# LEDs.net
KiCad netlist of a schematic drawn in Altium Designer
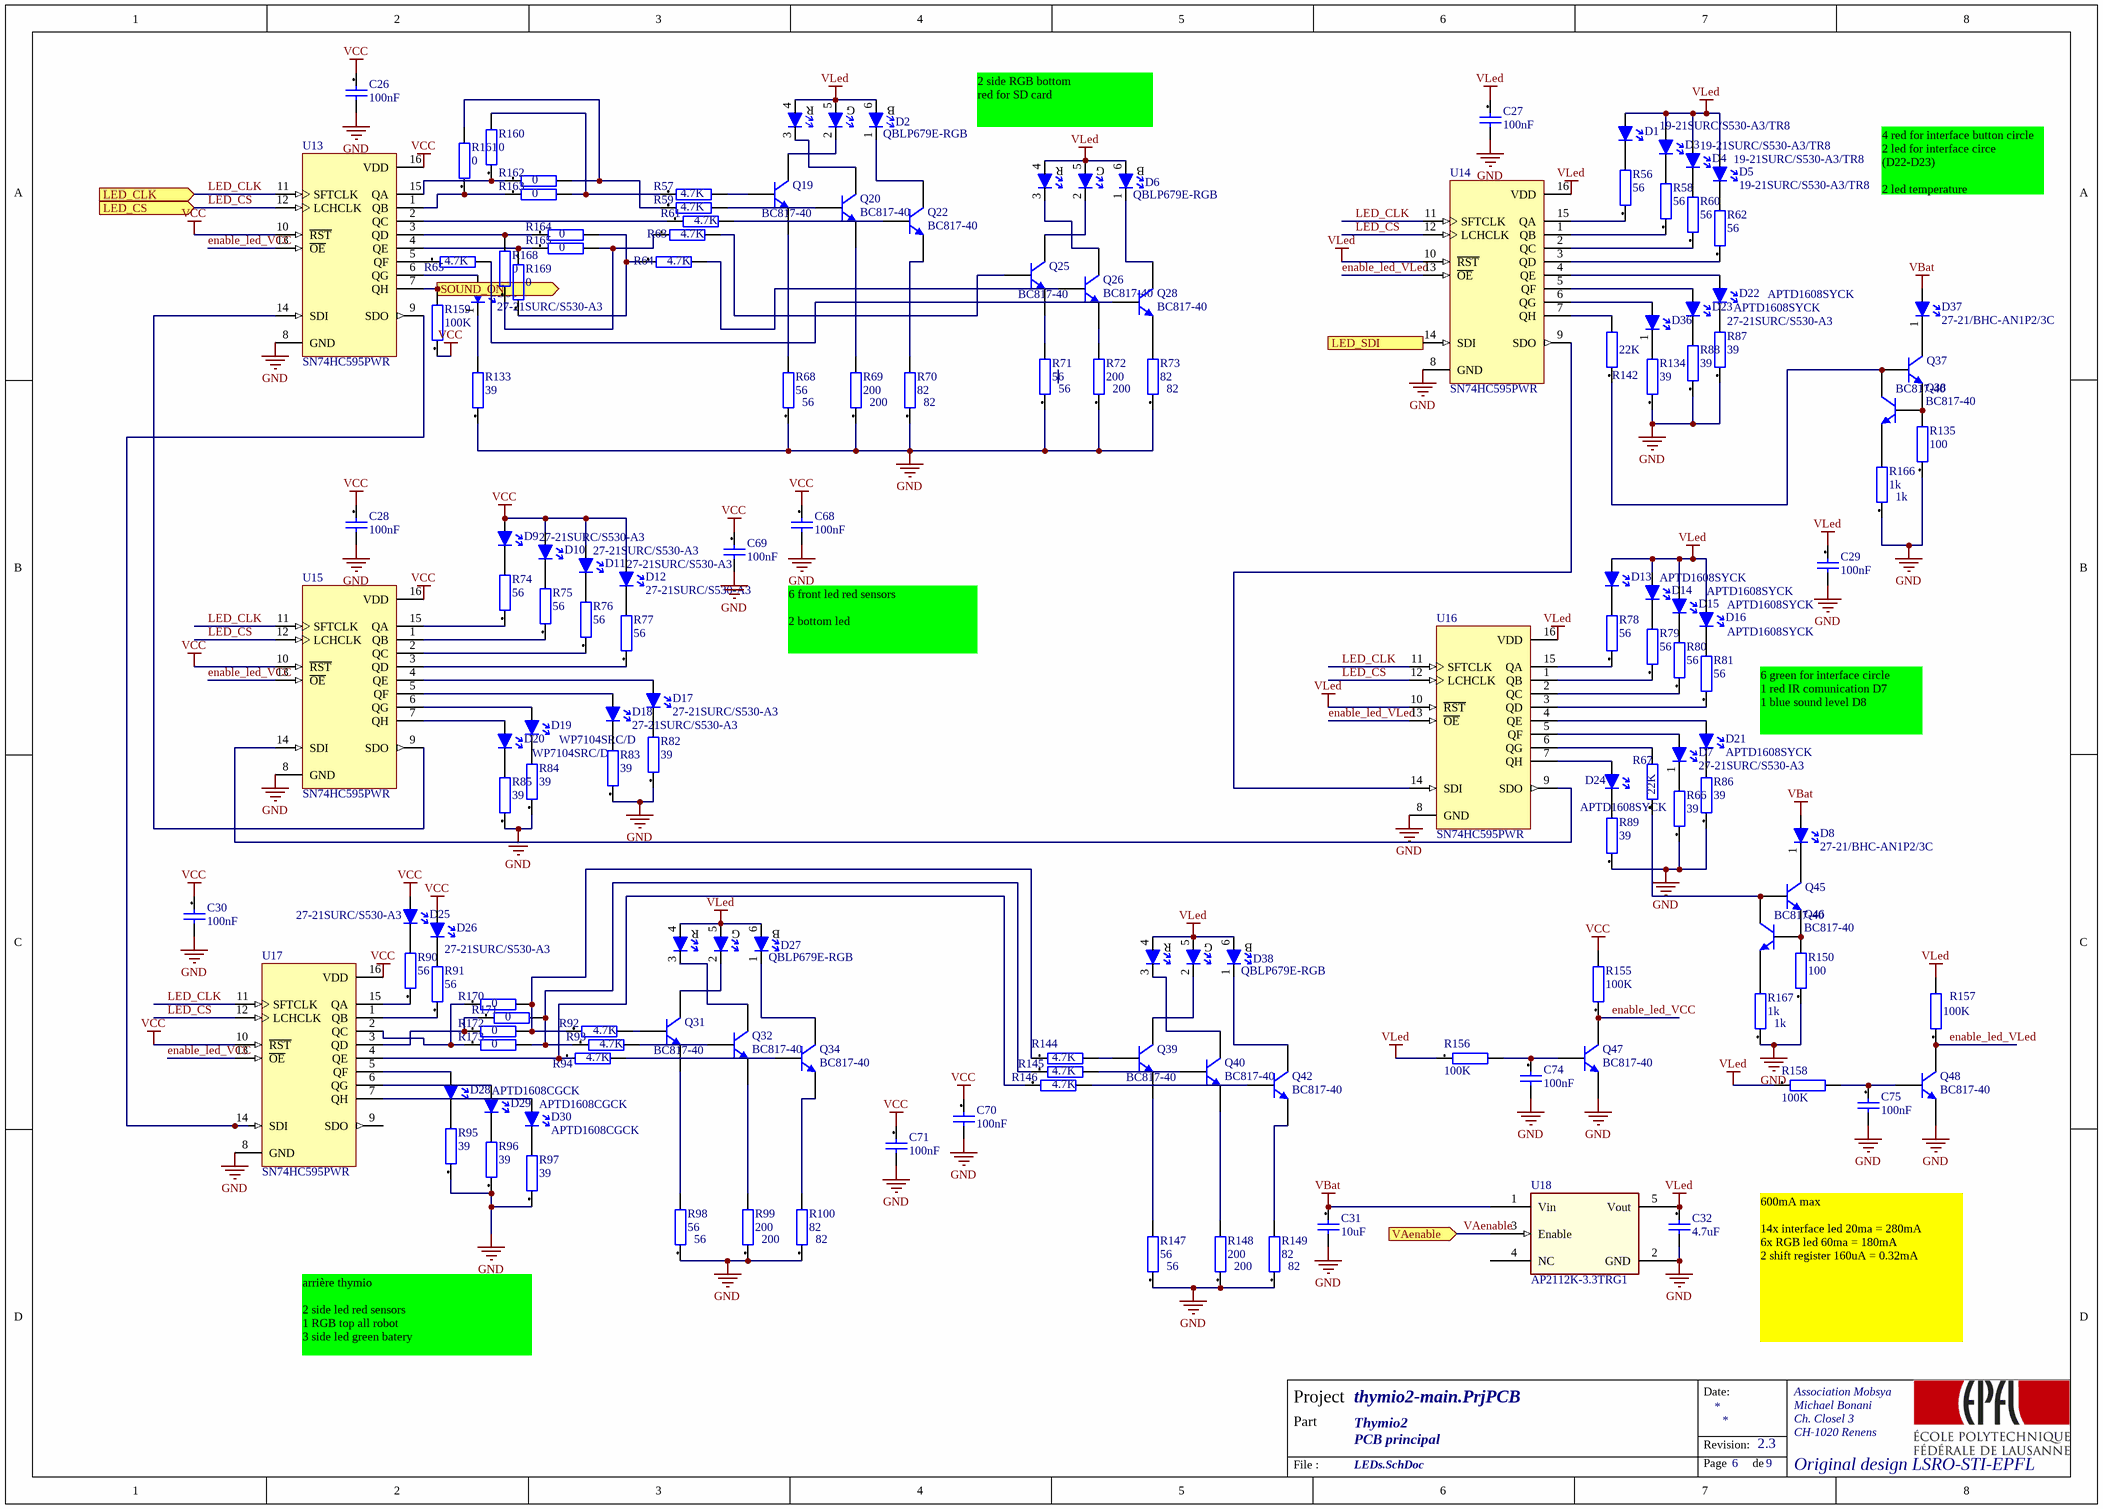
[diagram p0: LEDs.SchDoc]

(export (version "E")
  (design (tool "Eeschema 10.0.6"))
  (components
    (comp (ref "C26")
      (value "100nF")
      (footprint "CAPC1005X05N")
      (description "Capacitor")
      (fields (field (name "MANUFACTURER") "Kemet") (field (name "VOLTAGE") "50"))
      (libsource (lib "LSRO1Altium") (part "CAP-NP"))
    )
    (comp (ref "C27")
      (value "100nF")
      (footprint "CAPC1005X05N")
      (description "Capacitor")
      (fields (field (name "MANUFACTURER") "Kemet") (field (name "VOLTAGE") "50"))
      (libsource (lib "LSRO1Altium") (part "CAP-NP"))
    )
    (comp (ref "C28")
      (value "100nF")
      (footprint "CAPC1005X05N")
      (description "Capacitor")
      (fields (field (name "MANUFACTURER") "Kemet") (field (name "VOLTAGE") "50"))
      (libsource (lib "LSRO1Altium") (part "CAP-NP"))
    )
    (comp (ref "C29")
      (value "100nF")
      (footprint "CAPC1005X05N")
      (description "Capacitor")
      (fields (field (name "MANUFACTURER") "Kemet") (field (name "VOLTAGE") "50"))
      (libsource (lib "LSRO1Altium") (part "CAP-NP"))
    )
    (comp (ref "C30")
      (value "100nF")
      (footprint "CAPC1005X05N")
      (description "Capacitor")
      (fields (field (name "MANUFACTURER") "Kemet") (field (name "VOLTAGE") "50"))
      (libsource (lib "LSRO1Altium") (part "CAP-NP"))
    )
    (comp (ref "C31")
      (value "10uF")
      (footprint "CAPC1005X05N")
      (description "Capacitor")
      (fields (field (name "MANUFACTURER") "Kemet") (field (name "VOLTAGE") "6.3"))
      (libsource (lib "LSRO1Altium") (part "CAP-NP"))
    )
    (comp (ref "C32")
      (value "4.7uF")
      (footprint "CAPC1005X05N")
      (description "Capacitor")
      (fields (field (name "MANUFACTURER") "Kemet") (field (name "VOLTAGE") "6.3"))
      (libsource (lib "LSRO1Altium") (part "CAP-NP"))
    )
    (comp (ref "C68")
      (value "100nF")
      (footprint "CAPC1005X05N")
      (description "Capacitor")
      (fields (field (name "MANUFACTURER") "Kemet") (field (name "VOLTAGE") "50"))
      (libsource (lib "LSRO1Altium") (part "CAP-NP"))
    )
    (comp (ref "C69")
      (value "100nF")
      (footprint "CAPC1005X05N")
      (description "Capacitor")
      (fields (field (name "MANUFACTURER") "Kemet") (field (name "VOLTAGE") "50"))
      (libsource (lib "LSRO1Altium") (part "CAP-NP"))
    )
    (comp (ref "C70")
      (value "100nF")
      (footprint "CAPC1005X05N")
      (description "Capacitor")
      (fields (field (name "MANUFACTURER") "Kemet") (field (name "VOLTAGE") "50"))
      (libsource (lib "LSRO1Altium") (part "CAP-NP"))
    )
    (comp (ref "C71")
      (value "100nF")
      (footprint "CAPC1005X05N")
      (description "Capacitor")
      (fields (field (name "MANUFACTURER") "Kemet") (field (name "VOLTAGE") "50"))
      (libsource (lib "LSRO1Altium") (part "CAP-NP"))
    )
    (comp (ref "C74")
      (value "100nF")
      (footprint "CAPC1005X05N")
      (description "Capacitor")
      (fields (field (name "MANUFACTURER") "Kemet") (field (name "VOLTAGE") "50"))
      (libsource (lib "LSRO1Altium") (part "CAP-NP"))
    )
    (comp (ref "C75")
      (value "100nF")
      (footprint "CAPC1005X05N")
      (description "Capacitor")
      (fields (field (name "MANUFACTURER") "Kemet") (field (name "VOLTAGE") "50"))
      (libsource (lib "LSRO1Altium") (part "CAP-NP"))
    )
    (comp (ref "D1")
      (value "19-21SURC/S530-A3/TR8")
      (footprint "DIOC - DIOdeChip:DIOC1608X08N")
      (description "SMD Red 0603 2V@20ma 56 mcd")
      (fields (field (name "VERIFIEDCOMMENT") "ToDo"))
      (libsource (lib "LEDs") (part "LED"))
    )
    (comp (ref "D2")
      (value "QBLP679E-RGB")
      (footprint "thymio2-main:QBLP679E-RGB")
      (fields (field (name "VERIFIEDCOMMENT") "ToDo"))
      (libsource (lib "LEDs") (part "LED RGB SMD 2"))
    )
    (comp (ref "D3")
      (value "19-21SURC/S530-A3/TR8")
      (footprint "DIOC - DIOdeChip:DIOC1608X08N")
      (description "SMD Red 0603 2V@20ma 56 mcd")
      (fields (field (name "VERIFIEDCOMMENT") "ToDo"))
      (libsource (lib "LEDs") (part "LED"))
    )
    (comp (ref "D4")
      (value "19-21SURC/S530-A3/TR8")
      (footprint "DIOC - DIOdeChip:DIOC1608X08N")
      (description "SMD Red 0603 2V@20ma 56 mcd")
      (fields (field (name "VERIFIEDCOMMENT") "ToDo"))
      (libsource (lib "LEDs") (part "LED"))
    )
    (comp (ref "D5")
      (value "19-21SURC/S530-A3/TR8")
      (footprint "DIOC - DIOdeChip:DIOC1608X08N")
      (description "SMD Red 0603 2V@20ma 56 mcd")
      (fields (field (name "VERIFIEDCOMMENT") "ToDo"))
      (libsource (lib "LEDs") (part "LED"))
    )
    (comp (ref "D6")
      (value "QBLP679E-RGB")
      (footprint "thymio2-main:QBLP679E-RGB")
      (fields (field (name "VERIFIEDCOMMENT") "ToDo"))
      (libsource (lib "LEDs") (part "LED RGB SMD 2"))
    )
    (comp (ref "D7")
      (value "27-21SURC/S530-A3")
      (footprint "LEDs_Manufacturers:27-21 Everlight")
      (description "SMD Red led right angle mount 2V@20ma 57mcd")
      (fields (field (name "VERIFIEDCOMMENT") "ToDo"))
      (libsource (lib "") (part "LED_1"))
    )
    (comp (ref "D8")
      (value "27-21/BHC-AN1P2/3C")
      (footprint "LEDs_Manufacturers:27-21 Everlight Blue")
      (description "SMD Blue led right angle mount 3.3V@20ma 28mcd")
      (fields (field (name "VERIFIEDCOMMENT") "ToDo"))
      (libsource (lib "") (part "LED_1"))
    )
    (comp (ref "D9")
      (value "27-21SURC/S530-A3")
      (footprint "LEDs_Manufacturers:27-21 Everlight")
      (description "SMD Red led right angle mount 2V@20ma 57mcd")
      (fields (field (name "VERIFIEDCOMMENT") "ToDo"))
      (libsource (lib "LEDs") (part "LED"))
    )
    (comp (ref "D10")
      (value "27-21SURC/S530-A3")
      (footprint "LEDs_Manufacturers:27-21 Everlight")
      (description "SMD Red led right angle mount 2V@20ma 57mcd")
      (fields (field (name "VERIFIEDCOMMENT") "ToDo"))
      (libsource (lib "LEDs") (part "LED"))
    )
    (comp (ref "D11")
      (value "27-21SURC/S530-A3")
      (footprint "LEDs_Manufacturers:27-21 Everlight")
      (description "SMD Red led right angle mount 2V@20ma 57mcd")
      (fields (field (name "VERIFIEDCOMMENT") "ToDo"))
      (libsource (lib "LEDs") (part "LED"))
    )
    (comp (ref "D12")
      (value "27-21SURC/S530-A3")
      (footprint "LEDs_Manufacturers:27-21 Everlight")
      (description "SMD Red led right angle mount 2V@20ma 57mcd")
      (fields (field (name "VERIFIEDCOMMENT") "ToDo"))
      (libsource (lib "LEDs") (part "LED"))
    )
    (comp (ref "D13")
      (value "APTD1608SYCK")
      (footprint "DIOC - DIOdeChip:DIOC1608X08N")
      (description "LED standard - CMS Helios SMD Yellow 590nm 480mcd")
      (fields (field (name "VERIFIEDCOMMENT") "ToDo"))
      (libsource (lib "LEDs") (part "LED"))
    )
    (comp (ref "D14")
      (value "APTD1608SYCK")
      (footprint "DIOC - DIOdeChip:DIOC1608X08N")
      (description "LED standard - CMS Helios SMD Yellow 590nm 480mcd")
      (fields (field (name "VERIFIEDCOMMENT") "ToDo"))
      (libsource (lib "LEDs") (part "LED"))
    )
    (comp (ref "D15")
      (value "APTD1608SYCK")
      (footprint "DIOC - DIOdeChip:DIOC1608X08N")
      (description "LED standard - CMS Helios SMD Yellow 590nm 480mcd")
      (fields (field (name "VERIFIEDCOMMENT") "ToDo"))
      (libsource (lib "LEDs") (part "LED"))
    )
    (comp (ref "D16")
      (value "APTD1608SYCK")
      (footprint "DIOC - DIOdeChip:DIOC1608X08N")
      (description "LED standard - CMS Helios SMD Yellow 590nm 480mcd")
      (fields (field (name "VERIFIEDCOMMENT") "ToDo"))
      (libsource (lib "LEDs") (part "LED"))
    )
    (comp (ref "D17")
      (value "27-21SURC/S530-A3")
      (footprint "LEDs_Manufacturers:27-21 Everlight")
      (description "SMD Red led right angle mount 2V@20ma 57mcd")
      (fields (field (name "VERIFIEDCOMMENT") "ToDo"))
      (libsource (lib "LEDs") (part "LED"))
    )
    (comp (ref "D18")
      (value "27-21SURC/S530-A3")
      (footprint "LEDs_Manufacturers:27-21 Everlight")
      (description "SMD Red led right angle mount 2V@20ma 57mcd")
      (fields (field (name "VERIFIEDCOMMENT") "ToDo"))
      (libsource (lib "LEDs") (part "LED"))
    )
    (comp (ref "D19")
      (value "WP7104SRC/D")
      (footprint "LEDs_Manufacturers:Led_TH_3mm_20mm")
      (description "Red led 2V@20ma 57mcd")
      (fields (field (name "VERIFIEDCOMMENT") "ToDo"))
      (libsource (lib "LEDs") (part "LED"))
    )
    (comp (ref "D20")
      (value "WP7104SRC/D")
      (footprint "LEDs_Manufacturers:Led_TH_3mm_20mm")
      (description "Red led 2V@20ma 57mcd")
      (fields (field (name "VERIFIEDCOMMENT") "ToDo"))
      (libsource (lib "LEDs") (part "LED"))
    )
    (comp (ref "D21")
      (value "APTD1608SYCK")
      (footprint "DIOC - DIOdeChip:DIOC1608X08N")
      (description "LED standard - CMS Helios SMD Yellow 590nm 480mcd")
      (fields (field (name "VERIFIEDCOMMENT") "ToDo"))
      (libsource (lib "LEDs") (part "LED"))
    )
    (comp (ref "D22")
      (value "APTD1608SYCK")
      (footprint "DIOC - DIOdeChip:DIOC1608X08N")
      (description "LED standard - CMS Helios SMD Yellow 590nm 480mcd")
      (fields (field (name "VERIFIEDCOMMENT") "ToDo"))
      (libsource (lib "LEDs") (part "LED"))
    )
    (comp (ref "D23")
      (value "APTD1608SYCK")
      (footprint "DIOC - DIOdeChip:DIOC1608X08N")
      (description "LED standard - CMS Helios SMD Yellow 590nm 480mcd")
      (fields (field (name "VERIFIEDCOMMENT") "ToDo"))
      (libsource (lib "LEDs") (part "LED"))
    )
    (comp (ref "D24")
      (value "APTD1608SYCK")
      (footprint "DIOC - DIOdeChip:DIOC1608X08N")
      (description "LED standard - CMS Helios SMD Yellow 590nm 480mcd")
      (fields (field (name "VERIFIEDCOMMENT") "ToDo"))
      (libsource (lib "LEDs") (part "LED"))
    )
    (comp (ref "D25")
      (value "27-21SURC/S530-A3")
      (footprint "LEDs_Manufacturers:27-21 Everlight")
      (description "SMD Red led right angle mount 2V@20ma 57mcd")
      (fields (field (name "VERIFIEDCOMMENT") "ToDo"))
      (libsource (lib "LEDs") (part "LED"))
    )
    (comp (ref "D26")
      (value "27-21SURC/S530-A3")
      (footprint "LEDs_Manufacturers:27-21 Everlight")
      (description "SMD Red led right angle mount 2V@20ma 57mcd")
      (fields (field (name "VERIFIEDCOMMENT") "ToDo"))
      (libsource (lib "LEDs") (part "LED"))
    )
    (comp (ref "D27")
      (value "QBLP679E-RGB")
      (footprint "thymio2-main:QBLP679E-RGB")
      (fields (field (name "VERIFIEDCOMMENT") "ToDo"))
      (libsource (lib "LEDs") (part "LED RGB SMD 2"))
    )
    (comp (ref "D28")
      (value "APTD1608CGCK")
      (footprint "DIOC - DIOdeChip:DIOC1608X08N")
      (description "LED standard - CMS Helios SMD Green 570nm 230mcd")
      (fields (field (name "VERIFIEDCOMMENT") "ToDo"))
      (libsource (lib "LEDs") (part "LED"))
    )
    (comp (ref "D29")
      (value "APTD1608CGCK")
      (footprint "DIOC - DIOdeChip:DIOC1608X08N")
      (description "LED standard - CMS Helios SMD Green 570nm 230mcd")
      (fields (field (name "VERIFIEDCOMMENT") "ToDo"))
      (libsource (lib "LEDs") (part "LED"))
    )
    (comp (ref "D30")
      (value "APTD1608CGCK")
      (footprint "DIOC - DIOdeChip:DIOC1608X08N")
      (description "LED standard - CMS Helios SMD Green 570nm 230mcd")
      (fields (field (name "VERIFIEDCOMMENT") "ToDo"))
      (libsource (lib "LEDs") (part "LED"))
    )
    (comp (ref "D35")
      (value "27-21SURC/S530-A3")
      (footprint "LEDs_Manufacturers:27-21 Everlight")
      (description "SMD Red led right angle mount 2V@20ma 57mcd")
      (fields (field (name "VERIFIEDCOMMENT") "ToDo"))
      (libsource (lib "") (part "LED_1"))
    )
    (comp (ref "D36")
      (value "27-21SURC/S530-A3")
      (footprint "LEDs_Manufacturers:27-21 Everlight")
      (description "SMD Red led right angle mount 2V@20ma 57mcd")
      (fields (field (name "VERIFIEDCOMMENT") "ToDo"))
      (libsource (lib "") (part "LED_1"))
    )
    (comp (ref "D37")
      (value "27-21/BHC-AN1P2/3C")
      (footprint "LEDs_Manufacturers:27-21 Everlight Blue")
      (description "SMD Blue led right angle mount 3.3V@20ma 28mcd")
      (fields (field (name "VERIFIEDCOMMENT") "ToDo"))
      (libsource (lib "") (part "LED_1"))
    )
    (comp (ref "D38")
      (value "QBLP679E-RGB")
      (footprint "thymio2-main:QBLP679E-RGB")
      (fields (field (name "VERIFIEDCOMMENT") "ToDo"))
      (libsource (lib "LEDs") (part "LED RGB SMD 2"))
    )
    (comp (ref "Q19")
      (value "BC817-40")
      (footprint "SOT23_N")
      (description "NPN General-purpose Transistor")
      (fields (field (name "PUBLISHER") "Altium Limited"))
      (libsource (lib "Philips Discrete BJT - Low Power") (part "BC817-40"))
    )
    (comp (ref "Q20")
      (value "BC817-40")
      (footprint "SOT23_N")
      (description "NPN General-purpose Transistor")
      (fields (field (name "PUBLISHER") "Altium Limited"))
      (libsource (lib "Philips Discrete BJT - Low Power") (part "BC817-40"))
    )
    (comp (ref "Q22")
      (value "BC817-40")
      (footprint "SOT23_N")
      (description "NPN General-purpose Transistor")
      (fields (field (name "PUBLISHER") "Altium Limited"))
      (libsource (lib "Philips Discrete BJT - Low Power") (part "BC817-40"))
    )
    (comp (ref "Q25")
      (value "BC817-40")
      (footprint "SOT23_N")
      (description "NPN General-purpose Transistor")
      (fields (field (name "PUBLISHER") "Altium Limited"))
      (libsource (lib "Philips Discrete BJT - Low Power") (part "BC817-40"))
    )
    (comp (ref "Q26")
      (value "BC817-40")
      (footprint "SOT23_N")
      (description "NPN General-purpose Transistor")
      (fields (field (name "PUBLISHER") "Altium Limited"))
      (libsource (lib "Philips Discrete BJT - Low Power") (part "BC817-40"))
    )
    (comp (ref "Q28")
      (value "BC817-40")
      (footprint "SOT23_N")
      (description "NPN General-purpose Transistor")
      (fields (field (name "PUBLISHER") "Altium Limited"))
      (libsource (lib "Philips Discrete BJT - Low Power") (part "BC817-40"))
    )
    (comp (ref "Q31")
      (value "BC817-40")
      (footprint "SOT23_N")
      (description "NPN General-purpose Transistor")
      (fields (field (name "PUBLISHER") "Altium Limited"))
      (libsource (lib "Philips Discrete BJT - Low Power") (part "BC817-40"))
    )
    (comp (ref "Q32")
      (value "BC817-40")
      (footprint "SOT23_N")
      (description "NPN General-purpose Transistor")
      (fields (field (name "PUBLISHER") "Altium Limited"))
      (libsource (lib "Philips Discrete BJT - Low Power") (part "BC817-40"))
    )
    (comp (ref "Q34")
      (value "BC817-40")
      (footprint "SOT23_N")
      (description "NPN General-purpose Transistor")
      (fields (field (name "PUBLISHER") "Altium Limited"))
      (libsource (lib "Philips Discrete BJT - Low Power") (part "BC817-40"))
    )
    (comp (ref "Q37")
      (value "BC817-40")
      (footprint "SOT23_N")
      (description "NPN General-purpose Transistor")
      (fields (field (name "PUBLISHER") "Altium Limited"))
      (libsource (lib "Philips Discrete BJT - Low Power") (part "BC817-40"))
    )
    (comp (ref "Q38")
      (value "BC817-40")
      (footprint "SOT23_N")
      (description "NPN General-purpose Transistor")
      (fields (field (name "PUBLISHER") "Altium Limited"))
      (libsource (lib "Philips Discrete BJT - Low Power") (part "BC817-40"))
    )
    (comp (ref "Q39")
      (value "BC817-40")
      (footprint "SOT23_N")
      (description "NPN General-purpose Transistor")
      (fields (field (name "PUBLISHER") "Altium Limited"))
      (libsource (lib "Philips Discrete BJT - Low Power") (part "BC817-40"))
    )
    (comp (ref "Q40")
      (value "BC817-40")
      (footprint "SOT23_N")
      (description "NPN General-purpose Transistor")
      (fields (field (name "PUBLISHER") "Altium Limited"))
      (libsource (lib "Philips Discrete BJT - Low Power") (part "BC817-40"))
    )
    (comp (ref "Q42")
      (value "BC817-40")
      (footprint "SOT23_N")
      (description "NPN General-purpose Transistor")
      (fields (field (name "PUBLISHER") "Altium Limited"))
      (libsource (lib "Philips Discrete BJT - Low Power") (part "BC817-40"))
    )
    (comp (ref "Q45")
      (value "BC817-40")
      (footprint "SOT23_N")
      (description "NPN General-purpose Transistor")
      (fields (field (name "PUBLISHER") "Altium Limited"))
      (libsource (lib "Philips Discrete BJT - Low Power") (part "BC817-40"))
    )
    (comp (ref "Q46")
      (value "BC817-40")
      (footprint "SOT23_N")
      (description "NPN General-purpose Transistor")
      (fields (field (name "PUBLISHER") "Altium Limited"))
      (libsource (lib "Philips Discrete BJT - Low Power") (part "BC817-40"))
    )
    (comp (ref "Q47")
      (value "BC817-40")
      (footprint "SOT23_N")
      (description "NPN General-purpose Transistor")
      (fields (field (name "PUBLISHER") "Altium Limited"))
      (libsource (lib "Philips Discrete BJT - Low Power") (part "BC817-40"))
    )
    (comp (ref "Q48")
      (value "BC817-40")
      (footprint "SOT23_N")
      (description "NPN General-purpose Transistor")
      (fields (field (name "PUBLISHER") "Altium Limited"))
      (libsource (lib "Philips Discrete BJT - Low Power") (part "BC817-40"))
    )
    (comp (ref "R56")
      (value "56")
      (footprint "RESC1005X04N")
      (description "Resistor")
      (fields (field (name "TOLERANCE") "+/-1") (field (name "MANUFACTURER") "Vishay"))
      (libsource (lib "LSRO1Altium") (part "RES"))
    )
    (comp (ref "R57")
      (value "4.7K")
      (footprint "RESC1005X04N")
      (description "Resistor")
      (fields (field (name "TOLERANCE") "+/-1") (field (name "MANUFACTURER") "Vishay"))
      (libsource (lib "LSRO1Altium") (part "RES"))
    )
    (comp (ref "R58")
      (value "56")
      (footprint "RESC1005X04N")
      (description "Resistor")
      (fields (field (name "TOLERANCE") "+/-1") (field (name "MANUFACTURER") "Vishay"))
      (libsource (lib "LSRO1Altium") (part "RES"))
    )
    (comp (ref "R59")
      (value "4.7K")
      (footprint "RESC1005X04N")
      (description "Resistor")
      (fields (field (name "TOLERANCE") "+/-1") (field (name "MANUFACTURER") "Vishay"))
      (libsource (lib "LSRO1Altium") (part "RES"))
    )
    (comp (ref "R60")
      (value "56")
      (footprint "RESC1005X04N")
      (description "Resistor")
      (fields (field (name "TOLERANCE") "+/-1") (field (name "MANUFACTURER") "Vishay"))
      (libsource (lib "LSRO1Altium") (part "RES"))
    )
    (comp (ref "R61")
      (value "4.7K")
      (footprint "RESC1005X04N")
      (description "Resistor")
      (fields (field (name "TOLERANCE") "+/-1") (field (name "MANUFACTURER") "Vishay"))
      (libsource (lib "LSRO1Altium") (part "RES"))
    )
    (comp (ref "R62")
      (value "56")
      (footprint "RESC1005X04N")
      (description "Resistor")
      (fields (field (name "TOLERANCE") "+/-1") (field (name "MANUFACTURER") "Vishay"))
      (libsource (lib "LSRO1Altium") (part "RES"))
    )
    (comp (ref "R63")
      (value "4.7K")
      (footprint "RESC1005X04N")
      (description "Resistor")
      (fields (field (name "TOLERANCE") "+/-1") (field (name "MANUFACTURER") "Vishay"))
      (libsource (lib "LSRO1Altium") (part "RES"))
    )
    (comp (ref "R64")
      (value "4.7K")
      (footprint "RESC1005X04N")
      (description "Resistor")
      (fields (field (name "TOLERANCE") "+/-1") (field (name "MANUFACTURER") "Vishay"))
      (libsource (lib "LSRO1Altium") (part "RES"))
    )
    (comp (ref "R65")
      (value "4.7K")
      (footprint "RESC1005X04N")
      (description "Resistor")
      (fields (field (name "TOLERANCE") "+/-1") (field (name "MANUFACTURER") "Vishay"))
      (libsource (lib "LSRO1Altium") (part "RES"))
    )
    (comp (ref "R66")
      (value "39")
      (footprint "RESC1005X04N")
      (description "Resistor")
      (fields (field (name "TOLERANCE") "+/-1") (field (name "MANUFACTURER") "Vishay"))
      (libsource (lib "LSRO1Altium") (part "RES"))
    )
    (comp (ref "R67")
      (value "22K")
      (footprint "RESC1005X04N")
      (description "Resistor")
      (fields (field (name "TOLERANCE") "+/-1") (field (name "MANUFACTURER") "Vishay"))
      (libsource (lib "LSRO1Altium") (part "RES"))
    )
    (comp (ref "R68")
      (value "56")
      (footprint "RESC1005X04N")
      (fields (field (name "ALTIUM_VALUE") "56"))
      (libsource (lib "Passifs") (part "RES"))
    )
    (comp (ref "R69")
      (value "200")
      (footprint "RESC1005X04N")
      (fields (field (name "ALTIUM_VALUE") "200"))
      (libsource (lib "Passifs") (part "RES"))
    )
    (comp (ref "R70")
      (value "82")
      (footprint "RESC1005X04N")
      (fields (field (name "ALTIUM_VALUE") "82"))
      (libsource (lib "Passifs") (part "RES"))
    )
    (comp (ref "R71")
      (value "56")
      (footprint "RESC1005X04N")
      (fields (field (name "ALTIUM_VALUE") "56"))
      (libsource (lib "Passifs") (part "RES"))
    )
    (comp (ref "R72")
      (value "200")
      (footprint "RESC1005X04N")
      (fields (field (name "ALTIUM_VALUE") "200"))
      (libsource (lib "Passifs") (part "RES"))
    )
    (comp (ref "R73")
      (value "82")
      (footprint "RESC1005X04N")
      (fields (field (name "ALTIUM_VALUE") "82"))
      (libsource (lib "Passifs") (part "RES"))
    )
    (comp (ref "R74")
      (value "56")
      (footprint "RESC1005X04N")
      (description "Resistor")
      (fields (field (name "TOLERANCE") "+/-1") (field (name "MANUFACTURER") "Vishay"))
      (libsource (lib "LSRO1Altium") (part "RES"))
    )
    (comp (ref "R75")
      (value "56")
      (footprint "RESC1005X04N")
      (description "Resistor")
      (fields (field (name "TOLERANCE") "+/-1") (field (name "MANUFACTURER") "Vishay"))
      (libsource (lib "LSRO1Altium") (part "RES"))
    )
    (comp (ref "R76")
      (value "56")
      (footprint "RESC1005X04N")
      (description "Resistor")
      (fields (field (name "TOLERANCE") "+/-1") (field (name "MANUFACTURER") "Vishay"))
      (libsource (lib "LSRO1Altium") (part "RES"))
    )
    (comp (ref "R77")
      (value "56")
      (footprint "RESC1005X04N")
      (description "Resistor")
      (fields (field (name "TOLERANCE") "+/-1") (field (name "MANUFACTURER") "Vishay"))
      (libsource (lib "LSRO1Altium") (part "RES"))
    )
    (comp (ref "R78")
      (value "56")
      (footprint "RESC1005X04N")
      (description "Resistor")
      (fields (field (name "TOLERANCE") "+/-1") (field (name "MANUFACTURER") "Vishay"))
      (libsource (lib "LSRO1Altium") (part "RES"))
    )
    (comp (ref "R79")
      (value "56")
      (footprint "RESC1005X04N")
      (description "Resistor")
      (fields (field (name "TOLERANCE") "+/-1") (field (name "MANUFACTURER") "Vishay"))
      (libsource (lib "LSRO1Altium") (part "RES"))
    )
    (comp (ref "R80")
      (value "56")
      (footprint "RESC1005X04N")
      (description "Resistor")
      (fields (field (name "TOLERANCE") "+/-1") (field (name "MANUFACTURER") "Vishay"))
      (libsource (lib "LSRO1Altium") (part "RES"))
    )
    (comp (ref "R81")
      (value "56")
      (footprint "RESC1005X04N")
      (description "Resistor")
      (fields (field (name "TOLERANCE") "+/-1") (field (name "MANUFACTURER") "Vishay"))
      (libsource (lib "LSRO1Altium") (part "RES"))
    )
    (comp (ref "R82")
      (value "39")
      (footprint "RESC1005X04N")
      (description "Resistor")
      (fields (field (name "TOLERANCE") "+/-1") (field (name "MANUFACTURER") "Vishay"))
      (libsource (lib "LSRO1Altium") (part "RES"))
    )
    (comp (ref "R83")
      (value "39")
      (footprint "RESC1005X04N")
      (description "Resistor")
      (fields (field (name "TOLERANCE") "+/-1") (field (name "MANUFACTURER") "Vishay"))
      (libsource (lib "LSRO1Altium") (part "RES"))
    )
    (comp (ref "R84")
      (value "39")
      (footprint "RESC1005X04N")
      (description "Resistor")
      (fields (field (name "TOLERANCE") "+/-1") (field (name "MANUFACTURER") "Vishay"))
      (libsource (lib "LSRO1Altium") (part "RES"))
    )
    (comp (ref "R85")
      (value "39")
      (footprint "RESC1005X04N")
      (description "Resistor")
      (fields (field (name "TOLERANCE") "+/-1") (field (name "MANUFACTURER") "Vishay"))
      (libsource (lib "LSRO1Altium") (part "RES"))
    )
    (comp (ref "R86")
      (value "39")
      (footprint "RESC1005X04N")
      (description "Resistor")
      (fields (field (name "TOLERANCE") "+/-1") (field (name "MANUFACTURER") "Vishay"))
      (libsource (lib "LSRO1Altium") (part "RES"))
    )
    (comp (ref "R87")
      (value "39")
      (footprint "RESC1005X04N")
      (description "Resistor")
      (fields (field (name "TOLERANCE") "+/-1") (field (name "MANUFACTURER") "Vishay"))
      (libsource (lib "LSRO1Altium") (part "RES"))
    )
    (comp (ref "R88")
      (value "39")
      (footprint "RESC1005X04N")
      (description "Resistor")
      (fields (field (name "TOLERANCE") "+/-1") (field (name "MANUFACTURER") "Vishay"))
      (libsource (lib "LSRO1Altium") (part "RES"))
    )
    (comp (ref "R89")
      (value "39")
      (footprint "RESC1005X04N")
      (description "Resistor")
      (fields (field (name "TOLERANCE") "+/-1") (field (name "MANUFACTURER") "Vishay"))
      (libsource (lib "LSRO1Altium") (part "RES"))
    )
    (comp (ref "R90")
      (value "56")
      (footprint "RESC1005X04N")
      (description "Resistor")
      (fields (field (name "TOLERANCE") "+/-1") (field (name "MANUFACTURER") "Vishay"))
      (libsource (lib "LSRO1Altium") (part "RES"))
    )
    (comp (ref "R91")
      (value "56")
      (footprint "RESC1005X04N")
      (description "Resistor")
      (fields (field (name "TOLERANCE") "+/-1") (field (name "MANUFACTURER") "Vishay"))
      (libsource (lib "LSRO1Altium") (part "RES"))
    )
    (comp (ref "R92")
      (value "4.7K")
      (footprint "RESC1005X04N")
      (description "Resistor")
      (fields (field (name "TOLERANCE") "+/-1") (field (name "MANUFACTURER") "Vishay"))
      (libsource (lib "LSRO1Altium") (part "RES"))
    )
    (comp (ref "R93")
      (value "4.7K")
      (footprint "RESC1005X04N")
      (description "Resistor")
      (fields (field (name "TOLERANCE") "+/-1") (field (name "MANUFACTURER") "Vishay"))
      (libsource (lib "LSRO1Altium") (part "RES"))
    )
    (comp (ref "R94")
      (value "4.7K")
      (footprint "RESC1005X04N")
      (description "Resistor")
      (fields (field (name "TOLERANCE") "+/-1") (field (name "MANUFACTURER") "Vishay"))
      (libsource (lib "LSRO1Altium") (part "RES"))
    )
    (comp (ref "R95")
      (value "39")
      (footprint "RESC1005X04N")
      (description "Resistor")
      (fields (field (name "TOLERANCE") "+/-1") (field (name "MANUFACTURER") "Vishay"))
      (libsource (lib "LSRO1Altium") (part "RES"))
    )
    (comp (ref "R96")
      (value "39")
      (footprint "RESC1005X04N")
      (description "Resistor")
      (fields (field (name "TOLERANCE") "+/-1") (field (name "MANUFACTURER") "Vishay"))
      (libsource (lib "LSRO1Altium") (part "RES"))
    )
    (comp (ref "R97")
      (value "39")
      (footprint "RESC1005X04N")
      (description "Resistor")
      (fields (field (name "TOLERANCE") "+/-1") (field (name "MANUFACTURER") "Vishay"))
      (libsource (lib "LSRO1Altium") (part "RES"))
    )
    (comp (ref "R98")
      (value "56")
      (footprint "RESC1005X04N")
      (fields (field (name "ALTIUM_VALUE") "56"))
      (libsource (lib "Passifs") (part "RES"))
    )
    (comp (ref "R99")
      (value "200")
      (footprint "RESC1005X04N")
      (fields (field (name "ALTIUM_VALUE") "200"))
      (libsource (lib "Passifs") (part "RES"))
    )
    (comp (ref "R100")
      (value "82")
      (footprint "RESC1005X04N")
      (fields (field (name "ALTIUM_VALUE") "82"))
      (libsource (lib "Passifs") (part "RES"))
    )
    (comp (ref "R133")
      (value "39")
      (footprint "RESC1005X04N")
      (description "Resistor")
      (fields (field (name "TOLERANCE") "+/-1") (field (name "MANUFACTURER") "Vishay"))
      (libsource (lib "LSRO1Altium") (part "RES"))
    )
    (comp (ref "R134")
      (value "39")
      (footprint "RESC1005X04N")
      (description "Resistor")
      (fields (field (name "TOLERANCE") "+/-1") (field (name "MANUFACTURER") "Vishay"))
      (libsource (lib "LSRO1Altium") (part "RES"))
    )
    (comp (ref "R135")
      (value "100")
      (footprint "RESC1005X04N")
      (description "Resistor")
      (fields (field (name "TOLERANCE") "+/-1") (field (name "MANUFACTURER") "Vishay"))
      (libsource (lib "LSRO1Altium") (part "RES"))
    )
    (comp (ref "R142")
      (value "22K")
      (footprint "RESC1005X04N")
      (description "Resistor")
      (fields (field (name "TOLERANCE") "+/-1") (field (name "MANUFACTURER") "Vishay"))
      (libsource (lib "LSRO1Altium") (part "RES"))
    )
    (comp (ref "R144")
      (value "4.7K")
      (footprint "RESC1005X04N")
      (description "Resistor")
      (fields (field (name "TOLERANCE") "+/-1") (field (name "MANUFACTURER") "Vishay"))
      (libsource (lib "LSRO1Altium") (part "RES"))
    )
    (comp (ref "R145")
      (value "4.7K")
      (footprint "RESC1005X04N")
      (description "Resistor")
      (fields (field (name "TOLERANCE") "+/-1") (field (name "MANUFACTURER") "Vishay"))
      (libsource (lib "LSRO1Altium") (part "RES"))
    )
    (comp (ref "R146")
      (value "4.7K")
      (footprint "RESC1005X04N")
      (description "Resistor")
      (fields (field (name "TOLERANCE") "+/-1") (field (name "MANUFACTURER") "Vishay"))
      (libsource (lib "LSRO1Altium") (part "RES"))
    )
    (comp (ref "R147")
      (value "56")
      (footprint "RESC1005X04N")
      (fields (field (name "ALTIUM_VALUE") "56"))
      (libsource (lib "Passifs") (part "RES"))
    )
    (comp (ref "R148")
      (value "200")
      (footprint "RESC1005X04N")
      (fields (field (name "ALTIUM_VALUE") "200"))
      (libsource (lib "Passifs") (part "RES"))
    )
    (comp (ref "R149")
      (value "82")
      (footprint "RESC1005X04N")
      (fields (field (name "ALTIUM_VALUE") "82"))
      (libsource (lib "Passifs") (part "RES"))
    )
    (comp (ref "R150")
      (value "100")
      (footprint "RESC1005X04N")
      (description "Resistor")
      (fields (field (name "TOLERANCE") "+/-1") (field (name "MANUFACTURER") "Vishay"))
      (libsource (lib "LSRO1Altium") (part "RES"))
    )
    (comp (ref "R155")
      (value "100K")
      (footprint "RESC1005X04N")
      (description "Resistor")
      (fields (field (name "TOLERANCE") "+/-1") (field (name "MANUFACTURER") "Vishay"))
      (libsource (lib "LSRO1Altium") (part "RES"))
    )
    (comp (ref "R156")
      (value "100K")
      (footprint "RESC1005X04N")
      (description "Resistor")
      (fields (field (name "TOLERANCE") "+/-1") (field (name "MANUFACTURER") "Vishay"))
      (libsource (lib "LSRO1Altium") (part "RES"))
    )
    (comp (ref "R157")
      (value "100K")
      (footprint "RESC1005X04N")
      (description "Resistor")
      (fields (field (name "TOLERANCE") "+/-1") (field (name "MANUFACTURER") "Vishay"))
      (libsource (lib "LSRO1Altium") (part "RES"))
    )
    (comp (ref "R158")
      (value "100K")
      (footprint "RESC1005X04N")
      (description "Resistor")
      (fields (field (name "TOLERANCE") "+/-1") (field (name "MANUFACTURER") "Vishay"))
      (libsource (lib "LSRO1Altium") (part "RES"))
    )
    (comp (ref "R159")
      (value "100K")
      (footprint "RESC1005X04N")
      (description "Resistor")
      (fields (field (name "TOLERANCE") "+/-1") (field (name "MANUFACTURER") "Vishay"))
      (libsource (lib "LSRO1Altium") (part "RES"))
    )
    (comp (ref "R160")
      (value "0")
      (footprint "RESC1005X04N")
      (description "Resistor")
      (fields (field (name "TOLERANCE") "+/-1") (field (name "MANUFACTURER") "Vishay"))
      (libsource (lib "LSRO1Altium") (part "RES"))
    )
    (comp (ref "R161")
      (value "0")
      (footprint "RESC1005X04N")
      (description "Resistor")
      (fields (field (name "TOLERANCE") "+/-1") (field (name "MANUFACTURER") "Vishay"))
      (libsource (lib "LSRO1Altium") (part "RES"))
    )
    (comp (ref "R162")
      (value "0")
      (footprint "RESC1005X04N")
      (description "Resistor")
      (fields (field (name "TOLERANCE") "+/-1") (field (name "MANUFACTURER") "Vishay"))
      (libsource (lib "LSRO1Altium") (part "RES"))
    )
    (comp (ref "R163")
      (value "0")
      (footprint "RESC1005X04N")
      (description "Resistor")
      (fields (field (name "TOLERANCE") "+/-1") (field (name "MANUFACTURER") "Vishay"))
      (libsource (lib "LSRO1Altium") (part "RES"))
    )
    (comp (ref "R164")
      (value "0")
      (footprint "RESC1005X04N")
      (description "Resistor")
      (fields (field (name "TOLERANCE") "+/-1") (field (name "MANUFACTURER") "Vishay"))
      (libsource (lib "LSRO1Altium") (part "RES"))
    )
    (comp (ref "R165")
      (value "0")
      (footprint "RESC1005X04N")
      (description "Resistor")
      (fields (field (name "TOLERANCE") "+/-1") (field (name "MANUFACTURER") "Vishay"))
      (libsource (lib "LSRO1Altium") (part "RES"))
    )
    (comp (ref "R166")
      (value "1k")
      (footprint "RESC1005X04N")
      (description "120")
      (fields (field (name "ALTIUM_VALUE") "1k"))
      (libsource (lib "Passifs") (part "RES"))
    )
    (comp (ref "R167")
      (value "1k")
      (footprint "RESC1005X04N")
      (description "120")
      (fields (field (name "ALTIUM_VALUE") "1k"))
      (libsource (lib "Passifs") (part "RES"))
    )
    (comp (ref "R168")
      (value "0")
      (footprint "RESC1005X04N")
      (description "Resistor")
      (fields (field (name "TOLERANCE") "+/-1") (field (name "MANUFACTURER") "Vishay"))
      (libsource (lib "LSRO1Altium") (part "RES"))
    )
    (comp (ref "R169")
      (value "0")
      (footprint "RESC1005X04N")
      (description "Resistor")
      (fields (field (name "TOLERANCE") "+/-1") (field (name "MANUFACTURER") "Vishay"))
      (libsource (lib "LSRO1Altium") (part "RES"))
    )
    (comp (ref "R170")
      (value "0")
      (footprint "RESC1005X04N")
      (description "Resistor")
      (fields (field (name "TOLERANCE") "+/-1") (field (name "MANUFACTURER") "Vishay"))
      (libsource (lib "LSRO1Altium") (part "RES"))
    )
    (comp (ref "R171")
      (value "0")
      (footprint "RESC1005X04N")
      (description "Resistor")
      (fields (field (name "TOLERANCE") "+/-1") (field (name "MANUFACTURER") "Vishay"))
      (libsource (lib "LSRO1Altium") (part "RES"))
    )
    (comp (ref "R172")
      (value "0")
      (footprint "RESC1005X04N")
      (description "Resistor")
      (fields (field (name "TOLERANCE") "+/-1") (field (name "MANUFACTURER") "Vishay"))
      (libsource (lib "LSRO1Altium") (part "RES"))
    )
    (comp (ref "R173")
      (value "0")
      (footprint "RESC1005X04N")
      (description "Resistor")
      (fields (field (name "TOLERANCE") "+/-1") (field (name "MANUFACTURER") "Vishay"))
      (libsource (lib "LSRO1Altium") (part "RES"))
    )
    (comp (ref "U13")
      (value "SN74HC595PWR")
      (footprint "948F-01_N")
      (description "8-Bit Serial-Input/Serial or Prallel-Output Shift Register with Latched 3-State Outputs")
      (fields (field (name "PUBLISHER") "Altium Limited"))
      (libsource (lib "ON Semi Logic Register") (part "MC74HC595ADTR2"))
    )
    (comp (ref "U14")
      (value "SN74HC595PWR")
      (footprint "948F-01_N")
      (description "8-Bit Serial-Input/Serial or Prallel-Output Shift Register with Latched 3-State Outputs")
      (fields (field (name "PUBLISHER") "Altium Limited"))
      (libsource (lib "ON Semi Logic Register") (part "MC74HC595ADTR2"))
    )
    (comp (ref "U15")
      (value "SN74HC595PWR")
      (footprint "948F-01_N")
      (description "8-Bit Serial-Input/Serial or Prallel-Output Shift Register with Latched 3-State Outputs")
      (fields (field (name "PUBLISHER") "Altium Limited"))
      (libsource (lib "ON Semi Logic Register") (part "MC74HC595ADTR2"))
    )
    (comp (ref "U16")
      (value "SN74HC595PWR")
      (footprint "948F-01_N")
      (description "8-Bit Serial-Input/Serial or Prallel-Output Shift Register with Latched 3-State Outputs")
      (fields (field (name "PUBLISHER") "Altium Limited"))
      (libsource (lib "ON Semi Logic Register") (part "MC74HC595ADTR2"))
    )
    (comp (ref "U17")
      (value "SN74HC595PWR")
      (footprint "948F-01_N")
      (description "8-Bit Serial-Input/Serial or Prallel-Output Shift Register with Latched 3-State Outputs")
      (fields (field (name "PUBLISHER") "Altium Limited"))
      (libsource (lib "ON Semi Logic Register") (part "MC74HC595ADTR2"))
    )
    (comp (ref "U18")
      (value "AP2112K-3.3TRG1")
      (footprint "SOT - SmallOutlineTransistor:SOT95P285X100-5N")
      (description "300mA, Low Quiescent Current, Fast Transient LDO")
      (libsource (lib "ICs") (part "AP7331"))
    )
  )
  (nets
    (net (code "1") (name "/LED_CLK") (class "Default")
      (node (ref "U13") (pin "11") (pinfunction "SFTCLK_11") (pintype "input"))
      (node (ref "U14") (pin "11") (pinfunction "SFTCLK_11") (pintype "input"))
      (node (ref "U15") (pin "11") (pinfunction "SFTCLK_11") (pintype "input"))
      (node (ref "U16") (pin "11") (pinfunction "SFTCLK_11") (pintype "input"))
      (node (ref "U17") (pin "11") (pinfunction "SFTCLK_11") (pintype "input"))
    )
    (net (code "2") (name "/LED_CS") (class "Default")
      (node (ref "U13") (pin "12") (pinfunction "LCHCLK_12") (pintype "input"))
      (node (ref "U14") (pin "12") (pinfunction "LCHCLK_12") (pintype "input"))
      (node (ref "U15") (pin "12") (pinfunction "LCHCLK_12") (pintype "input"))
      (node (ref "U16") (pin "12") (pinfunction "LCHCLK_12") (pintype "input"))
      (node (ref "U17") (pin "12") (pinfunction "LCHCLK_12") (pintype "input"))
    )
    (net (code "3") (name "/LED_SDI") (class "Default")
      (node (ref "U14") (pin "14") (pinfunction "SDI_14") (pintype "input"))
    )
    (net (code "4") (name "/SOUND_ON") (class "Default")
      (node (ref "R159") (pin "2") (pinfunction "2_2") (pintype "passive"))
      (node (ref "U13") (pin "7") (pinfunction "QH_7") (pintype "tri_state"))
    )
    (net (code "5") (name "/VAenable") (class "Default")
      (node (ref "U18") (pin "3") (pinfunction "Enable_3") (pintype "input"))
    )
    (net (code "6") (name "/enable_led_VCC") (class "Default")
      (node (ref "Q47") (pin "3") (pinfunction "C_3") (pintype "passive"))
      (node (ref "R155") (pin "1") (pinfunction "1_1") (pintype "passive"))
      (node (ref "U13") (pin "13") (pinfunction "~{OE}_13") (pintype "input"))
      (node (ref "U15") (pin "13") (pinfunction "~{OE}_13") (pintype "input"))
      (node (ref "U17") (pin "13") (pinfunction "~{OE}_13") (pintype "input"))
    )
    (net (code "7") (name "/enable_led_VLed") (class "Default")
      (node (ref "Q48") (pin "3") (pinfunction "C_3") (pintype "passive"))
      (node (ref "R157") (pin "1") (pinfunction "1_1") (pintype "passive"))
      (node (ref "U14") (pin "13") (pinfunction "~{OE}_13") (pintype "input"))
      (node (ref "U16") (pin "13") (pinfunction "~{OE}_13") (pintype "input"))
    )
    (net (code "8") (name "GND") (class "Default")
      (node (ref "C26") (pin "2") (pinfunction "2_2") (pintype "passive"))
      (node (ref "C27") (pin "2") (pinfunction "2_2") (pintype "passive"))
      (node (ref "C28") (pin "2") (pinfunction "2_2") (pintype "passive"))
      (node (ref "C29") (pin "2") (pinfunction "2_2") (pintype "passive"))
      (node (ref "C30") (pin "2") (pinfunction "2_2") (pintype "passive"))
      (node (ref "C31") (pin "2") (pinfunction "2_2") (pintype "passive"))
      (node (ref "C32") (pin "2") (pinfunction "2_2") (pintype "passive"))
      (node (ref "C68") (pin "2") (pinfunction "2_2") (pintype "passive"))
      (node (ref "C69") (pin "2") (pinfunction "2_2") (pintype "passive"))
      (node (ref "C70") (pin "2") (pinfunction "2_2") (pintype "passive"))
      (node (ref "C71") (pin "2") (pinfunction "2_2") (pintype "passive"))
      (node (ref "C74") (pin "2") (pinfunction "2_2") (pintype "passive"))
      (node (ref "C75") (pin "2") (pinfunction "2_2") (pintype "passive"))
      (node (ref "Q47") (pin "2") (pinfunction "E_2") (pintype "passive"))
      (node (ref "Q48") (pin "2") (pinfunction "E_2") (pintype "passive"))
      (node (ref "R100") (pin "1") (pinfunction "1_1") (pintype "passive"))
      (node (ref "R133") (pin "1") (pinfunction "1_1") (pintype "passive"))
      (node (ref "R134") (pin "1") (pinfunction "1_1") (pintype "passive"))
      (node (ref "R135") (pin "1") (pinfunction "1_1") (pintype "passive"))
      (node (ref "R147") (pin "1") (pinfunction "1_1") (pintype "passive"))
      (node (ref "R148") (pin "1") (pinfunction "1_1") (pintype "passive"))
      (node (ref "R149") (pin "1") (pinfunction "1_1") (pintype "passive"))
      (node (ref "R150") (pin "1") (pinfunction "1_1") (pintype "passive"))
      (node (ref "R166") (pin "1") (pinfunction "1_1") (pintype "passive"))
      (node (ref "R167") (pin "1") (pinfunction "1_1") (pintype "passive"))
      (node (ref "R66") (pin "1") (pinfunction "1_1") (pintype "passive"))
      (node (ref "R68") (pin "1") (pinfunction "1_1") (pintype "passive"))
      (node (ref "R69") (pin "1") (pinfunction "1_1") (pintype "passive"))
      (node (ref "R70") (pin "1") (pinfunction "1_1") (pintype "passive"))
      (node (ref "R71") (pin "1") (pinfunction "1_1") (pintype "passive"))
      (node (ref "R72") (pin "1") (pinfunction "1_1") (pintype "passive"))
      (node (ref "R73") (pin "1") (pinfunction "1_1") (pintype "passive"))
      (node (ref "R82") (pin "1") (pinfunction "1_1") (pintype "passive"))
      (node (ref "R83") (pin "1") (pinfunction "1_1") (pintype "passive"))
      (node (ref "R84") (pin "1") (pinfunction "1_1") (pintype "passive"))
      (node (ref "R85") (pin "1") (pinfunction "1_1") (pintype "passive"))
      (node (ref "R86") (pin "1") (pinfunction "1_1") (pintype "passive"))
      (node (ref "R87") (pin "1") (pinfunction "1_1") (pintype "passive"))
      (node (ref "R88") (pin "1") (pinfunction "1_1") (pintype "passive"))
      (node (ref "R89") (pin "1") (pinfunction "1_1") (pintype "passive"))
      (node (ref "R95") (pin "1") (pinfunction "1_1") (pintype "passive"))
      (node (ref "R96") (pin "1") (pinfunction "1_1") (pintype "passive"))
      (node (ref "R97") (pin "1") (pinfunction "1_1") (pintype "passive"))
      (node (ref "R98") (pin "1") (pinfunction "1_1") (pintype "passive"))
      (node (ref "R99") (pin "1") (pinfunction "1_1") (pintype "passive"))
      (node (ref "U13") (pin "8") (pinfunction "GND_8") (pintype "power_in"))
      (node (ref "U14") (pin "8") (pinfunction "GND_8") (pintype "power_in"))
      (node (ref "U15") (pin "8") (pinfunction "GND_8") (pintype "power_in"))
      (node (ref "U16") (pin "8") (pinfunction "GND_8") (pintype "power_in"))
      (node (ref "U17") (pin "8") (pinfunction "GND_8") (pintype "power_in"))
      (node (ref "U18") (pin "2") (pinfunction "GND_2") (pintype "power_in"))
    )
    (net (code "9") (name "Net-(D1-K)") (class "Default")
      (node (ref "D1") (pin "1") (pinfunction "K_1") (pintype "passive"))
      (node (ref "R56") (pin "2") (pinfunction "2_2") (pintype "passive"))
    )
    (net (code "10") (name "Net-(D2-Kb)") (class "Default")
      (node (ref "D2") (pin "1") (pinfunction "Kb_1") (pintype "passive"))
      (node (ref "Q22") (pin "3") (pinfunction "C_3") (pintype "passive"))
    )
    (net (code "11") (name "Net-(D2-Kg)") (class "Default")
      (node (ref "D2") (pin "2") (pinfunction "Kg_2") (pintype "passive"))
      (node (ref "Q19") (pin "3") (pinfunction "C_3") (pintype "passive"))
    )
    (net (code "12") (name "Net-(D2-Kr)") (class "Default")
      (node (ref "D2") (pin "3") (pinfunction "Kr_3") (pintype "passive"))
      (node (ref "Q20") (pin "3") (pinfunction "C_3") (pintype "passive"))
    )
    (net (code "13") (name "Net-(D3-K)") (class "Default")
      (node (ref "D3") (pin "1") (pinfunction "K_1") (pintype "passive"))
      (node (ref "R58") (pin "2") (pinfunction "2_2") (pintype "passive"))
    )
    (net (code "14") (name "Net-(D4-K)") (class "Default")
      (node (ref "D4") (pin "1") (pinfunction "K_1") (pintype "passive"))
      (node (ref "R60") (pin "2") (pinfunction "2_2") (pintype "passive"))
    )
    (net (code "15") (name "Net-(D5-K)") (class "Default")
      (node (ref "D5") (pin "1") (pinfunction "K_1") (pintype "passive"))
      (node (ref "R62") (pin "2") (pinfunction "2_2") (pintype "passive"))
    )
    (net (code "16") (name "Net-(D6-Kb)") (class "Default")
      (node (ref "D6") (pin "1") (pinfunction "Kb_1") (pintype "passive"))
      (node (ref "Q28") (pin "3") (pinfunction "C_3") (pintype "passive"))
    )
    (net (code "17") (name "Net-(D6-Kg)") (class "Default")
      (node (ref "D6") (pin "2") (pinfunction "Kg_2") (pintype "passive"))
      (node (ref "Q25") (pin "3") (pinfunction "C_3") (pintype "passive"))
    )
    (net (code "18") (name "Net-(D6-Kr)") (class "Default")
      (node (ref "D6") (pin "3") (pinfunction "Kr_3") (pintype "passive"))
      (node (ref "Q26") (pin "3") (pinfunction "C_3") (pintype "passive"))
    )
    (net (code "19") (name "Net-(D7-A)") (class "Default")
      (node (ref "D7") (pin "2") (pinfunction "A_2") (pintype "passive"))
      (node (ref "U16") (pin "5") (pinfunction "QF_5") (pintype "tri_state"))
    )
    (net (code "20") (name "Net-(D7-K)") (class "Default")
      (node (ref "D7") (pin "1") (pinfunction "K_1") (pintype "passive"))
      (node (ref "R66") (pin "2") (pinfunction "2_2") (pintype "passive"))
    )
    (net (code "21") (name "Net-(D8-K)") (class "Default")
      (node (ref "D8") (pin "1") (pinfunction "K_1") (pintype "passive"))
      (node (ref "Q45") (pin "3") (pinfunction "C_3") (pintype "passive"))
    )
    (net (code "22") (name "Net-(D9-K)") (class "Default")
      (node (ref "D9") (pin "1") (pinfunction "K_1") (pintype "passive"))
      (node (ref "R74") (pin "2") (pinfunction "2_2") (pintype "passive"))
    )
    (net (code "23") (name "Net-(D10-K)") (class "Default")
      (node (ref "D10") (pin "1") (pinfunction "K_1") (pintype "passive"))
      (node (ref "R75") (pin "2") (pinfunction "2_2") (pintype "passive"))
    )
    (net (code "24") (name "Net-(D11-K)") (class "Default")
      (node (ref "D11") (pin "1") (pinfunction "K_1") (pintype "passive"))
      (node (ref "R76") (pin "2") (pinfunction "2_2") (pintype "passive"))
    )
    (net (code "25") (name "Net-(D12-K)") (class "Default")
      (node (ref "D12") (pin "1") (pinfunction "K_1") (pintype "passive"))
      (node (ref "R77") (pin "2") (pinfunction "2_2") (pintype "passive"))
    )
    (net (code "26") (name "Net-(D13-K)") (class "Default")
      (node (ref "D13") (pin "1") (pinfunction "K_1") (pintype "passive"))
      (node (ref "R78") (pin "2") (pinfunction "2_2") (pintype "passive"))
    )
    (net (code "27") (name "Net-(D14-K)") (class "Default")
      (node (ref "D14") (pin "1") (pinfunction "K_1") (pintype "passive"))
      (node (ref "R79") (pin "2") (pinfunction "2_2") (pintype "passive"))
    )
    (net (code "28") (name "Net-(D15-K)") (class "Default")
      (node (ref "D15") (pin "1") (pinfunction "K_1") (pintype "passive"))
      (node (ref "R80") (pin "2") (pinfunction "2_2") (pintype "passive"))
    )
    (net (code "29") (name "Net-(D16-K)") (class "Default")
      (node (ref "D16") (pin "1") (pinfunction "K_1") (pintype "passive"))
      (node (ref "R81") (pin "2") (pinfunction "2_2") (pintype "passive"))
    )
    (net (code "30") (name "Net-(D17-A)") (class "Default")
      (node (ref "D17") (pin "2") (pinfunction "A_2") (pintype "passive"))
      (node (ref "U15") (pin "4") (pinfunction "QE_4") (pintype "tri_state"))
    )
    (net (code "31") (name "Net-(D17-K)") (class "Default")
      (node (ref "D17") (pin "1") (pinfunction "K_1") (pintype "passive"))
      (node (ref "R82") (pin "2") (pinfunction "2_2") (pintype "passive"))
    )
    (net (code "32") (name "Net-(D18-A)") (class "Default")
      (node (ref "D18") (pin "2") (pinfunction "A_2") (pintype "passive"))
      (node (ref "U15") (pin "5") (pinfunction "QF_5") (pintype "tri_state"))
    )
    (net (code "33") (name "Net-(D18-K)") (class "Default")
      (node (ref "D18") (pin "1") (pinfunction "K_1") (pintype "passive"))
      (node (ref "R83") (pin "2") (pinfunction "2_2") (pintype "passive"))
    )
    (net (code "34") (name "Net-(D19-A)") (class "Default")
      (node (ref "D19") (pin "2") (pinfunction "A_2") (pintype "passive"))
      (node (ref "U15") (pin "6") (pinfunction "QG_6") (pintype "tri_state"))
    )
    (net (code "35") (name "Net-(D19-K)") (class "Default")
      (node (ref "D19") (pin "1") (pinfunction "K_1") (pintype "passive"))
      (node (ref "R84") (pin "2") (pinfunction "2_2") (pintype "passive"))
    )
    (net (code "36") (name "Net-(D20-A)") (class "Default")
      (node (ref "D20") (pin "2") (pinfunction "A_2") (pintype "passive"))
      (node (ref "U15") (pin "7") (pinfunction "QH_7") (pintype "tri_state"))
    )
    (net (code "37") (name "Net-(D20-K)") (class "Default")
      (node (ref "D20") (pin "1") (pinfunction "K_1") (pintype "passive"))
      (node (ref "R85") (pin "2") (pinfunction "2_2") (pintype "passive"))
    )
    (net (code "38") (name "Net-(D21-A)") (class "Default")
      (node (ref "D21") (pin "2") (pinfunction "A_2") (pintype "passive"))
      (node (ref "U16") (pin "4") (pinfunction "QE_4") (pintype "tri_state"))
    )
    (net (code "39") (name "Net-(D21-K)") (class "Default")
      (node (ref "D21") (pin "1") (pinfunction "K_1") (pintype "passive"))
      (node (ref "R86") (pin "2") (pinfunction "2_2") (pintype "passive"))
    )
    (net (code "40") (name "Net-(D22-A)") (class "Default")
      (node (ref "D22") (pin "2") (pinfunction "A_2") (pintype "passive"))
      (node (ref "U14") (pin "4") (pinfunction "QE_4") (pintype "tri_state"))
    )
    (net (code "41") (name "Net-(D22-K)") (class "Default")
      (node (ref "D22") (pin "1") (pinfunction "K_1") (pintype "passive"))
      (node (ref "R87") (pin "2") (pinfunction "2_2") (pintype "passive"))
    )
    (net (code "42") (name "Net-(D23-A)") (class "Default")
      (node (ref "D23") (pin "2") (pinfunction "A_2") (pintype "passive"))
      (node (ref "U14") (pin "5") (pinfunction "QF_5") (pintype "tri_state"))
    )
    (net (code "43") (name "Net-(D23-K)") (class "Default")
      (node (ref "D23") (pin "1") (pinfunction "K_1") (pintype "passive"))
      (node (ref "R88") (pin "2") (pinfunction "2_2") (pintype "passive"))
    )
    (net (code "44") (name "Net-(D24-A)") (class "Default")
      (node (ref "D24") (pin "2") (pinfunction "A_2") (pintype "passive"))
      (node (ref "U16") (pin "7") (pinfunction "QH_7") (pintype "tri_state"))
    )
    (net (code "45") (name "Net-(D24-K)") (class "Default")
      (node (ref "D24") (pin "1") (pinfunction "K_1") (pintype "passive"))
      (node (ref "R89") (pin "2") (pinfunction "2_2") (pintype "passive"))
    )
    (net (code "46") (name "Net-(D25-K)") (class "Default")
      (node (ref "D25") (pin "1") (pinfunction "K_1") (pintype "passive"))
      (node (ref "R90") (pin "2") (pinfunction "2_2") (pintype "passive"))
    )
    (net (code "47") (name "Net-(D26-K)") (class "Default")
      (node (ref "D26") (pin "1") (pinfunction "K_1") (pintype "passive"))
      (node (ref "R91") (pin "2") (pinfunction "2_2") (pintype "passive"))
    )
    (net (code "48") (name "Net-(D27-Kb)") (class "Default")
      (node (ref "D27") (pin "1") (pinfunction "Kb_1") (pintype "passive"))
      (node (ref "Q34") (pin "3") (pinfunction "C_3") (pintype "passive"))
    )
    (net (code "49") (name "Net-(D27-Kg)") (class "Default")
      (node (ref "D27") (pin "2") (pinfunction "Kg_2") (pintype "passive"))
      (node (ref "Q31") (pin "3") (pinfunction "C_3") (pintype "passive"))
    )
    (net (code "50") (name "Net-(D27-Kr)") (class "Default")
      (node (ref "D27") (pin "3") (pinfunction "Kr_3") (pintype "passive"))
      (node (ref "Q32") (pin "3") (pinfunction "C_3") (pintype "passive"))
    )
    (net (code "51") (name "Net-(D28-A)") (class "Default")
      (node (ref "D28") (pin "2") (pinfunction "A_2") (pintype "passive"))
      (node (ref "U17") (pin "5") (pinfunction "QF_5") (pintype "tri_state"))
    )
    (net (code "52") (name "Net-(D28-K)") (class "Default")
      (node (ref "D28") (pin "1") (pinfunction "K_1") (pintype "passive"))
      (node (ref "R95") (pin "2") (pinfunction "2_2") (pintype "passive"))
    )
    (net (code "53") (name "Net-(D29-A)") (class "Default")
      (node (ref "D29") (pin "2") (pinfunction "A_2") (pintype "passive"))
      (node (ref "U17") (pin "6") (pinfunction "QG_6") (pintype "tri_state"))
    )
    (net (code "54") (name "Net-(D29-K)") (class "Default")
      (node (ref "D29") (pin "1") (pinfunction "K_1") (pintype "passive"))
      (node (ref "R96") (pin "2") (pinfunction "2_2") (pintype "passive"))
    )
    (net (code "55") (name "Net-(D30-A)") (class "Default")
      (node (ref "D30") (pin "2") (pinfunction "A_2") (pintype "passive"))
      (node (ref "U17") (pin "7") (pinfunction "QH_7") (pintype "tri_state"))
    )
    (net (code "56") (name "Net-(D30-K)") (class "Default")
      (node (ref "D30") (pin "1") (pinfunction "K_1") (pintype "passive"))
      (node (ref "R97") (pin "2") (pinfunction "2_2") (pintype "passive"))
    )
    (net (code "57") (name "Net-(D35-A)") (class "Default")
      (node (ref "D35") (pin "2") (pinfunction "A_2") (pintype "passive"))
      (node (ref "U13") (pin "6") (pinfunction "QG_6") (pintype "tri_state"))
    )
    (net (code "58") (name "Net-(D35-K)") (class "Default")
      (node (ref "D35") (pin "1") (pinfunction "K_1") (pintype "passive"))
      (node (ref "R133") (pin "2") (pinfunction "2_2") (pintype "passive"))
    )
    (net (code "59") (name "Net-(D36-A)") (class "Default")
      (node (ref "D36") (pin "2") (pinfunction "A_2") (pintype "passive"))
      (node (ref "U14") (pin "6") (pinfunction "QG_6") (pintype "tri_state"))
    )
    (net (code "60") (name "Net-(D36-K)") (class "Default")
      (node (ref "D36") (pin "1") (pinfunction "K_1") (pintype "passive"))
      (node (ref "R134") (pin "2") (pinfunction "2_2") (pintype "passive"))
    )
    (net (code "61") (name "Net-(D37-K)") (class "Default")
      (node (ref "D37") (pin "1") (pinfunction "K_1") (pintype "passive"))
      (node (ref "Q37") (pin "3") (pinfunction "C_3") (pintype "passive"))
    )
    (net (code "62") (name "Net-(D38-Kb)") (class "Default")
      (node (ref "D38") (pin "1") (pinfunction "Kb_1") (pintype "passive"))
      (node (ref "Q42") (pin "3") (pinfunction "C_3") (pintype "passive"))
    )
    (net (code "63") (name "Net-(D38-Kg)") (class "Default")
      (node (ref "D38") (pin "2") (pinfunction "Kg_2") (pintype "passive"))
      (node (ref "Q39") (pin "3") (pinfunction "C_3") (pintype "passive"))
    )
    (net (code "64") (name "Net-(D38-Kr)") (class "Default")
      (node (ref "D38") (pin "3") (pinfunction "Kr_3") (pintype "passive"))
      (node (ref "Q40") (pin "3") (pinfunction "C_3") (pintype "passive"))
    )
    (net (code "65") (name "Net-(Q19-B)") (class "Default")
      (node (ref "Q19") (pin "1") (pinfunction "B_1") (pintype "passive"))
      (node (ref "R57") (pin "2") (pinfunction "2_2") (pintype "passive"))
    )
    (net (code "66") (name "Net-(Q19-E)") (class "Default")
      (node (ref "Q19") (pin "2") (pinfunction "E_2") (pintype "passive"))
      (node (ref "R68") (pin "2") (pinfunction "2_2") (pintype "passive"))
    )
    (net (code "67") (name "Net-(Q20-B)") (class "Default")
      (node (ref "Q20") (pin "1") (pinfunction "B_1") (pintype "passive"))
      (node (ref "R59") (pin "2") (pinfunction "2_2") (pintype "passive"))
    )
    (net (code "68") (name "Net-(Q20-E)") (class "Default")
      (node (ref "Q20") (pin "2") (pinfunction "E_2") (pintype "passive"))
      (node (ref "R69") (pin "2") (pinfunction "2_2") (pintype "passive"))
    )
    (net (code "69") (name "Net-(Q22-B)") (class "Default")
      (node (ref "Q22") (pin "1") (pinfunction "B_1") (pintype "passive"))
      (node (ref "R61") (pin "2") (pinfunction "2_2") (pintype "passive"))
    )
    (net (code "70") (name "Net-(Q22-E)") (class "Default")
      (node (ref "Q22") (pin "2") (pinfunction "E_2") (pintype "passive"))
      (node (ref "R70") (pin "2") (pinfunction "2_2") (pintype "passive"))
    )
    (net (code "71") (name "Net-(Q25-B)") (class "Default")
      (node (ref "Q25") (pin "1") (pinfunction "B_1") (pintype "passive"))
      (node (ref "R63") (pin "2") (pinfunction "2_2") (pintype "passive"))
    )
    (net (code "72") (name "Net-(Q25-E)") (class "Default")
      (node (ref "Q25") (pin "2") (pinfunction "E_2") (pintype "passive"))
      (node (ref "R71") (pin "2") (pinfunction "2_2") (pintype "passive"))
    )
    (net (code "73") (name "Net-(Q26-B)") (class "Default")
      (node (ref "Q26") (pin "1") (pinfunction "B_1") (pintype "passive"))
      (node (ref "R64") (pin "2") (pinfunction "2_2") (pintype "passive"))
    )
    (net (code "74") (name "Net-(Q26-E)") (class "Default")
      (node (ref "Q26") (pin "2") (pinfunction "E_2") (pintype "passive"))
      (node (ref "R72") (pin "2") (pinfunction "2_2") (pintype "passive"))
    )
    (net (code "75") (name "Net-(Q28-B)") (class "Default")
      (node (ref "Q28") (pin "1") (pinfunction "B_1") (pintype "passive"))
      (node (ref "R65") (pin "2") (pinfunction "2_2") (pintype "passive"))
    )
    (net (code "76") (name "Net-(Q28-E)") (class "Default")
      (node (ref "Q28") (pin "2") (pinfunction "E_2") (pintype "passive"))
      (node (ref "R73") (pin "2") (pinfunction "2_2") (pintype "passive"))
    )
    (net (code "77") (name "Net-(Q31-B)") (class "Default")
      (node (ref "Q31") (pin "1") (pinfunction "B_1") (pintype "passive"))
      (node (ref "R92") (pin "2") (pinfunction "2_2") (pintype "passive"))
    )
    (net (code "78") (name "Net-(Q31-E)") (class "Default")
      (node (ref "Q31") (pin "2") (pinfunction "E_2") (pintype "passive"))
      (node (ref "R98") (pin "2") (pinfunction "2_2") (pintype "passive"))
    )
    (net (code "79") (name "Net-(Q32-B)") (class "Default")
      (node (ref "Q32") (pin "1") (pinfunction "B_1") (pintype "passive"))
      (node (ref "R93") (pin "2") (pinfunction "2_2") (pintype "passive"))
    )
    (net (code "80") (name "Net-(Q32-E)") (class "Default")
      (node (ref "Q32") (pin "2") (pinfunction "E_2") (pintype "passive"))
      (node (ref "R99") (pin "2") (pinfunction "2_2") (pintype "passive"))
    )
    (net (code "81") (name "Net-(Q34-B)") (class "Default")
      (node (ref "Q34") (pin "1") (pinfunction "B_1") (pintype "passive"))
      (node (ref "R94") (pin "2") (pinfunction "2_2") (pintype "passive"))
    )
    (net (code "82") (name "Net-(Q34-E)") (class "Default")
      (node (ref "Q34") (pin "2") (pinfunction "E_2") (pintype "passive"))
      (node (ref "R100") (pin "2") (pinfunction "2_2") (pintype "passive"))
    )
    (net (code "83") (name "Net-(Q37-B)") (class "Default")
      (node (ref "Q37") (pin "1") (pinfunction "B_1") (pintype "passive"))
      (node (ref "Q38") (pin "3") (pinfunction "C_3") (pintype "passive"))
      (node (ref "R142") (pin "1") (pinfunction "1_1") (pintype "passive"))
    )
    (net (code "84") (name "Net-(Q37-E)") (class "Default")
      (node (ref "Q37") (pin "2") (pinfunction "E_2") (pintype "passive"))
      (node (ref "Q38") (pin "1") (pinfunction "B_1") (pintype "passive"))
      (node (ref "R135") (pin "2") (pinfunction "2_2") (pintype "passive"))
    )
    (net (code "85") (name "Net-(Q38-E)") (class "Default")
      (node (ref "Q38") (pin "2") (pinfunction "E_2") (pintype "passive"))
      (node (ref "R166") (pin "2") (pinfunction "2_2") (pintype "passive"))
    )
    (net (code "86") (name "Net-(Q39-B)") (class "Default")
      (node (ref "Q39") (pin "1") (pinfunction "B_1") (pintype "passive"))
      (node (ref "R144") (pin "2") (pinfunction "2_2") (pintype "passive"))
    )
    (net (code "87") (name "Net-(Q39-E)") (class "Default")
      (node (ref "Q39") (pin "2") (pinfunction "E_2") (pintype "passive"))
      (node (ref "R147") (pin "2") (pinfunction "2_2") (pintype "passive"))
    )
    (net (code "88") (name "Net-(Q40-B)") (class "Default")
      (node (ref "Q40") (pin "1") (pinfunction "B_1") (pintype "passive"))
      (node (ref "R145") (pin "2") (pinfunction "2_2") (pintype "passive"))
    )
    (net (code "89") (name "Net-(Q40-E)") (class "Default")
      (node (ref "Q40") (pin "2") (pinfunction "E_2") (pintype "passive"))
      (node (ref "R148") (pin "2") (pinfunction "2_2") (pintype "passive"))
    )
    (net (code "90") (name "Net-(Q42-B)") (class "Default")
      (node (ref "Q42") (pin "1") (pinfunction "B_1") (pintype "passive"))
      (node (ref "R146") (pin "2") (pinfunction "2_2") (pintype "passive"))
    )
    (net (code "91") (name "Net-(Q42-E)") (class "Default")
      (node (ref "Q42") (pin "2") (pinfunction "E_2") (pintype "passive"))
      (node (ref "R149") (pin "2") (pinfunction "2_2") (pintype "passive"))
    )
    (net (code "92") (name "Net-(Q45-B)") (class "Default")
      (node (ref "Q45") (pin "1") (pinfunction "B_1") (pintype "passive"))
      (node (ref "Q46") (pin "3") (pinfunction "C_3") (pintype "passive"))
      (node (ref "R67") (pin "1") (pinfunction "1_1") (pintype "passive"))
    )
    (net (code "93") (name "Net-(Q45-E)") (class "Default")
      (node (ref "Q45") (pin "2") (pinfunction "E_2") (pintype "passive"))
      (node (ref "Q46") (pin "1") (pinfunction "B_1") (pintype "passive"))
      (node (ref "R150") (pin "2") (pinfunction "2_2") (pintype "passive"))
    )
    (net (code "94") (name "Net-(Q46-E)") (class "Default")
      (node (ref "Q46") (pin "2") (pinfunction "E_2") (pintype "passive"))
      (node (ref "R167") (pin "2") (pinfunction "2_2") (pintype "passive"))
    )
    (net (code "95") (name "Net-(Q47-B)") (class "Default")
      (node (ref "C74") (pin "1") (pinfunction "1_1") (pintype "passive"))
      (node (ref "Q47") (pin "1") (pinfunction "B_1") (pintype "passive"))
      (node (ref "R156") (pin "2") (pinfunction "2_2") (pintype "passive"))
    )
    (net (code "96") (name "Net-(Q48-B)") (class "Default")
      (node (ref "C75") (pin "1") (pinfunction "1_1") (pintype "passive"))
      (node (ref "Q48") (pin "1") (pinfunction "B_1") (pintype "passive"))
      (node (ref "R158") (pin "2") (pinfunction "2_2") (pintype "passive"))
    )
    (net (code "97") (name "Net-(R144-Pad1)") (class "Default")
      (node (ref "R144") (pin "1") (pinfunction "1_1") (pintype "passive"))
      (node (ref "R170") (pin "2") (pinfunction "2_2") (pintype "passive"))
      (node (ref "R172") (pin "2") (pinfunction "2_2") (pintype "passive"))
      (node (ref "R92") (pin "1") (pinfunction "1_1") (pintype "passive"))
    )
    (net (code "98") (name "Net-(R145-Pad1)") (class "Default")
      (node (ref "R145") (pin "1") (pinfunction "1_1") (pintype "passive"))
      (node (ref "R171") (pin "2") (pinfunction "2_2") (pintype "passive"))
      (node (ref "R173") (pin "2") (pinfunction "2_2") (pintype "passive"))
      (node (ref "R93") (pin "1") (pinfunction "1_1") (pintype "passive"))
    )
    (net (code "99") (name "Net-(R160-Pad2)") (class "Default")
      (node (ref "R160") (pin "2") (pinfunction "2_2") (pintype "passive"))
      (node (ref "R163") (pin "2") (pinfunction "2_2") (pintype "passive"))
      (node (ref "R57") (pin "1") (pinfunction "1_1") (pintype "passive"))
    )
    (net (code "100") (name "Net-(R161-Pad2)") (class "Default")
      (node (ref "R161") (pin "2") (pinfunction "2_2") (pintype "passive"))
      (node (ref "R162") (pin "2") (pinfunction "2_2") (pintype "passive"))
      (node (ref "R59") (pin "1") (pinfunction "1_1") (pintype "passive"))
    )
    (net (code "101") (name "Net-(R164-Pad2)") (class "Default")
      (node (ref "R164") (pin "2") (pinfunction "2_2") (pintype "passive"))
      (node (ref "R169") (pin "1") (pinfunction "1_1") (pintype "passive"))
      (node (ref "R64") (pin "1") (pinfunction "1_1") (pintype "passive"))
    )
    (net (code "102") (name "Net-(R165-Pad2)") (class "Default")
      (node (ref "R165") (pin "2") (pinfunction "2_2") (pintype "passive"))
      (node (ref "R168") (pin "1") (pinfunction "1_1") (pintype "passive"))
      (node (ref "R63") (pin "1") (pinfunction "1_1") (pintype "passive"))
    )
    (net (code "103") (name "Net-(U13-QA)") (class "Default")
      (node (ref "R160") (pin "1") (pinfunction "1_1") (pintype "passive"))
      (node (ref "R162") (pin "1") (pinfunction "1_1") (pintype "passive"))
      (node (ref "U13") (pin "15") (pinfunction "QA_15") (pintype "tri_state"))
    )
    (net (code "104") (name "Net-(U13-QB)") (class "Default")
      (node (ref "R161") (pin "1") (pinfunction "1_1") (pintype "passive"))
      (node (ref "R163") (pin "1") (pinfunction "1_1") (pintype "passive"))
      (node (ref "U13") (pin "1") (pinfunction "QB_1") (pintype "tri_state"))
    )
    (net (code "105") (name "Net-(U13-QC)") (class "Default")
      (node (ref "R61") (pin "1") (pinfunction "1_1") (pintype "passive"))
      (node (ref "U13") (pin "2") (pinfunction "QC_2") (pintype "tri_state"))
    )
    (net (code "106") (name "Net-(U13-QD)") (class "Default")
      (node (ref "R164") (pin "1") (pinfunction "1_1") (pintype "passive"))
      (node (ref "R168") (pin "2") (pinfunction "2_2") (pintype "passive"))
      (node (ref "U13") (pin "3") (pinfunction "QD_3") (pintype "tri_state"))
    )
    (net (code "107") (name "Net-(U13-QE)") (class "Default")
      (node (ref "R165") (pin "1") (pinfunction "1_1") (pintype "passive"))
      (node (ref "R169") (pin "2") (pinfunction "2_2") (pintype "passive"))
      (node (ref "U13") (pin "4") (pinfunction "QE_4") (pintype "tri_state"))
    )
    (net (code "108") (name "Net-(U13-QF)") (class "Default")
      (node (ref "R65") (pin "1") (pinfunction "1_1") (pintype "passive"))
      (node (ref "U13") (pin "5") (pinfunction "QF_5") (pintype "tri_state"))
    )
    (net (code "109") (name "Net-(U13-SDI)") (class "Default")
      (node (ref "U13") (pin "14") (pinfunction "SDI_14") (pintype "input"))
      (node (ref "U15") (pin "9") (pinfunction "SDO_9") (pintype "output"))
    )
    (net (code "110") (name "Net-(U13-SDO)") (class "Default")
      (node (ref "U13") (pin "9") (pinfunction "SDO_9") (pintype "output"))
      (node (ref "U17") (pin "14") (pinfunction "SDI_14") (pintype "input"))
    )
    (net (code "111") (name "Net-(U14-QA)") (class "Default")
      (node (ref "R56") (pin "1") (pinfunction "1_1") (pintype "passive"))
      (node (ref "U14") (pin "15") (pinfunction "QA_15") (pintype "tri_state"))
    )
    (net (code "112") (name "Net-(U14-QB)") (class "Default")
      (node (ref "R58") (pin "1") (pinfunction "1_1") (pintype "passive"))
      (node (ref "U14") (pin "1") (pinfunction "QB_1") (pintype "tri_state"))
    )
    (net (code "113") (name "Net-(U14-QC)") (class "Default")
      (node (ref "R60") (pin "1") (pinfunction "1_1") (pintype "passive"))
      (node (ref "U14") (pin "2") (pinfunction "QC_2") (pintype "tri_state"))
    )
    (net (code "114") (name "Net-(U14-QD)") (class "Default")
      (node (ref "R62") (pin "1") (pinfunction "1_1") (pintype "passive"))
      (node (ref "U14") (pin "3") (pinfunction "QD_3") (pintype "tri_state"))
    )
    (net (code "115") (name "Net-(U14-QH)") (class "Default")
      (node (ref "R142") (pin "2") (pinfunction "2_2") (pintype "passive"))
      (node (ref "U14") (pin "7") (pinfunction "QH_7") (pintype "tri_state"))
    )
    (net (code "116") (name "Net-(U14-SDO)") (class "Default")
      (node (ref "U14") (pin "9") (pinfunction "SDO_9") (pintype "output"))
      (node (ref "U16") (pin "14") (pinfunction "SDI_14") (pintype "input"))
    )
    (net (code "117") (name "Net-(U15-QA)") (class "Default")
      (node (ref "R74") (pin "1") (pinfunction "1_1") (pintype "passive"))
      (node (ref "U15") (pin "15") (pinfunction "QA_15") (pintype "tri_state"))
    )
    (net (code "118") (name "Net-(U15-QB)") (class "Default")
      (node (ref "R75") (pin "1") (pinfunction "1_1") (pintype "passive"))
      (node (ref "U15") (pin "1") (pinfunction "QB_1") (pintype "tri_state"))
    )
    (net (code "119") (name "Net-(U15-QC)") (class "Default")
      (node (ref "R76") (pin "1") (pinfunction "1_1") (pintype "passive"))
      (node (ref "U15") (pin "2") (pinfunction "QC_2") (pintype "tri_state"))
    )
    (net (code "120") (name "Net-(U15-QD)") (class "Default")
      (node (ref "R77") (pin "1") (pinfunction "1_1") (pintype "passive"))
      (node (ref "U15") (pin "3") (pinfunction "QD_3") (pintype "tri_state"))
    )
    (net (code "121") (name "Net-(U15-SDI)") (class "Default")
      (node (ref "U15") (pin "14") (pinfunction "SDI_14") (pintype "input"))
      (node (ref "U16") (pin "9") (pinfunction "SDO_9") (pintype "output"))
    )
    (net (code "122") (name "Net-(U16-QA)") (class "Default")
      (node (ref "R78") (pin "1") (pinfunction "1_1") (pintype "passive"))
      (node (ref "U16") (pin "15") (pinfunction "QA_15") (pintype "tri_state"))
    )
    (net (code "123") (name "Net-(U16-QB)") (class "Default")
      (node (ref "R79") (pin "1") (pinfunction "1_1") (pintype "passive"))
      (node (ref "U16") (pin "1") (pinfunction "QB_1") (pintype "tri_state"))
    )
    (net (code "124") (name "Net-(U16-QC)") (class "Default")
      (node (ref "R80") (pin "1") (pinfunction "1_1") (pintype "passive"))
      (node (ref "U16") (pin "2") (pinfunction "QC_2") (pintype "tri_state"))
    )
    (net (code "125") (name "Net-(U16-QD)") (class "Default")
      (node (ref "R81") (pin "1") (pinfunction "1_1") (pintype "passive"))
      (node (ref "U16") (pin "3") (pinfunction "QD_3") (pintype "tri_state"))
    )
    (net (code "126") (name "Net-(U16-QG)") (class "Default")
      (node (ref "R67") (pin "2") (pinfunction "2_2") (pintype "passive"))
      (node (ref "U16") (pin "6") (pinfunction "QG_6") (pintype "tri_state"))
    )
    (net (code "127") (name "Net-(U17-QA)") (class "Default")
      (node (ref "R90") (pin "1") (pinfunction "1_1") (pintype "passive"))
      (node (ref "U17") (pin "15") (pinfunction "QA_15") (pintype "tri_state"))
    )
    (net (code "128") (name "Net-(U17-QB)") (class "Default")
      (node (ref "R91") (pin "1") (pinfunction "1_1") (pintype "passive"))
      (node (ref "U17") (pin "1") (pinfunction "QB_1") (pintype "tri_state"))
    )
    (net (code "129") (name "Net-(U17-QC)") (class "Default")
      (node (ref "R170") (pin "1") (pinfunction "1_1") (pintype "passive"))
      (node (ref "R173") (pin "1") (pinfunction "1_1") (pintype "passive"))
      (node (ref "U17") (pin "2") (pinfunction "QC_2") (pintype "tri_state"))
    )
    (net (code "130") (name "Net-(U17-QD)") (class "Default")
      (node (ref "R171") (pin "1") (pinfunction "1_1") (pintype "passive"))
      (node (ref "R172") (pin "1") (pinfunction "1_1") (pintype "passive"))
      (node (ref "U17") (pin "3") (pinfunction "QD_3") (pintype "tri_state"))
    )
    (net (code "131") (name "Net-(U17-QE)") (class "Default")
      (node (ref "R146") (pin "1") (pinfunction "1_1") (pintype "passive"))
      (node (ref "R94") (pin "1") (pinfunction "1_1") (pintype "passive"))
      (node (ref "U17") (pin "4") (pinfunction "QE_4") (pintype "tri_state"))
    )
    (net (code "132") (name "VBat") (class "Default")
      (node (ref "C31") (pin "1") (pinfunction "1_1") (pintype "passive"))
      (node (ref "D37") (pin "2") (pinfunction "A_2") (pintype "passive"))
      (node (ref "D8") (pin "2") (pinfunction "A_2") (pintype "passive"))
      (node (ref "U18") (pin "1") (pinfunction "Vin_1") (pintype "power_in"))
    )
    (net (code "133") (name "VCC") (class "Default")
      (node (ref "C26") (pin "1") (pinfunction "1_1") (pintype "passive"))
      (node (ref "C28") (pin "1") (pinfunction "1_1") (pintype "passive"))
      (node (ref "C30") (pin "1") (pinfunction "1_1") (pintype "passive"))
      (node (ref "C68") (pin "1") (pinfunction "1_1") (pintype "passive"))
      (node (ref "C69") (pin "1") (pinfunction "1_1") (pintype "passive"))
      (node (ref "C70") (pin "1") (pinfunction "1_1") (pintype "passive"))
      (node (ref "C71") (pin "1") (pinfunction "1_1") (pintype "passive"))
      (node (ref "D10") (pin "2") (pinfunction "A_2") (pintype "passive"))
      (node (ref "D11") (pin "2") (pinfunction "A_2") (pintype "passive"))
      (node (ref "D12") (pin "2") (pinfunction "A_2") (pintype "passive"))
      (node (ref "D25") (pin "2") (pinfunction "A_2") (pintype "passive"))
      (node (ref "D26") (pin "2") (pinfunction "A_2") (pintype "passive"))
      (node (ref "D9") (pin "2") (pinfunction "A_2") (pintype "passive"))
      (node (ref "R155") (pin "2") (pinfunction "2_2") (pintype "passive"))
      (node (ref "R159") (pin "1") (pinfunction "1_1") (pintype "passive"))
      (node (ref "U13") (pin "10") (pinfunction "~{RST}_10") (pintype "input"))
      (node (ref "U13") (pin "16") (pinfunction "VDD_16") (pintype "power_in"))
      (node (ref "U15") (pin "10") (pinfunction "~{RST}_10") (pintype "input"))
      (node (ref "U15") (pin "16") (pinfunction "VDD_16") (pintype "power_in"))
      (node (ref "U17") (pin "10") (pinfunction "~{RST}_10") (pintype "input"))
      (node (ref "U17") (pin "16") (pinfunction "VDD_16") (pintype "power_in"))
    )
    (net (code "134") (name "VLed") (class "Default")
      (node (ref "C27") (pin "1") (pinfunction "1_1") (pintype "passive"))
      (node (ref "C29") (pin "1") (pinfunction "1_1") (pintype "passive"))
      (node (ref "C32") (pin "1") (pinfunction "1_1") (pintype "passive"))
      (node (ref "D1") (pin "2") (pinfunction "A_2") (pintype "passive"))
      (node (ref "D13") (pin "2") (pinfunction "A_2") (pintype "passive"))
      (node (ref "D14") (pin "2") (pinfunction "A_2") (pintype "passive"))
      (node (ref "D15") (pin "2") (pinfunction "A_2") (pintype "passive"))
      (node (ref "D16") (pin "2") (pinfunction "A_2") (pintype "passive"))
      (node (ref "D2") (pin "4") (pinfunction "Ar_4") (pintype "passive"))
      (node (ref "D2") (pin "5") (pinfunction "Ag_5") (pintype "passive"))
      (node (ref "D2") (pin "6") (pinfunction "Ab_6") (pintype "passive"))
      (node (ref "D27") (pin "4") (pinfunction "Ar_4") (pintype "passive"))
      (node (ref "D27") (pin "5") (pinfunction "Ag_5") (pintype "passive"))
      (node (ref "D27") (pin "6") (pinfunction "Ab_6") (pintype "passive"))
      (node (ref "D3") (pin "2") (pinfunction "A_2") (pintype "passive"))
      (node (ref "D38") (pin "4") (pinfunction "Ar_4") (pintype "passive"))
      (node (ref "D38") (pin "5") (pinfunction "Ag_5") (pintype "passive"))
      (node (ref "D38") (pin "6") (pinfunction "Ab_6") (pintype "passive"))
      (node (ref "D4") (pin "2") (pinfunction "A_2") (pintype "passive"))
      (node (ref "D5") (pin "2") (pinfunction "A_2") (pintype "passive"))
      (node (ref "D6") (pin "4") (pinfunction "Ar_4") (pintype "passive"))
      (node (ref "D6") (pin "5") (pinfunction "Ag_5") (pintype "passive"))
      (node (ref "D6") (pin "6") (pinfunction "Ab_6") (pintype "passive"))
      (node (ref "R156") (pin "1") (pinfunction "1_1") (pintype "passive"))
      (node (ref "R157") (pin "2") (pinfunction "2_2") (pintype "passive"))
      (node (ref "R158") (pin "1") (pinfunction "1_1") (pintype "passive"))
      (node (ref "U14") (pin "10") (pinfunction "~{RST}_10") (pintype "input"))
      (node (ref "U14") (pin "16") (pinfunction "VDD_16") (pintype "power_in"))
      (node (ref "U16") (pin "10") (pinfunction "~{RST}_10") (pintype "input"))
      (node (ref "U16") (pin "16") (pinfunction "VDD_16") (pintype "power_in"))
      (node (ref "U18") (pin "5") (pinfunction "Vout_5") (pintype "power_in"))
    )
    (net (code "135") (name "unconnected-(U17-SDO-Pad9)") (class "Default")
      (node (ref "U17") (pin "9") (pinfunction "SDO_9") (pintype "output"))
    )
    (net (code "136") (name "unconnected-(U18-NC-Pad4)") (class "Default")
      (node (ref "U18") (pin "4") (pinfunction "NC_4") (pintype "passive"))
    )
  )
)
